# Poactuator_Connectors.net
KiCad netlist of a schematic drawn in Altium Designer
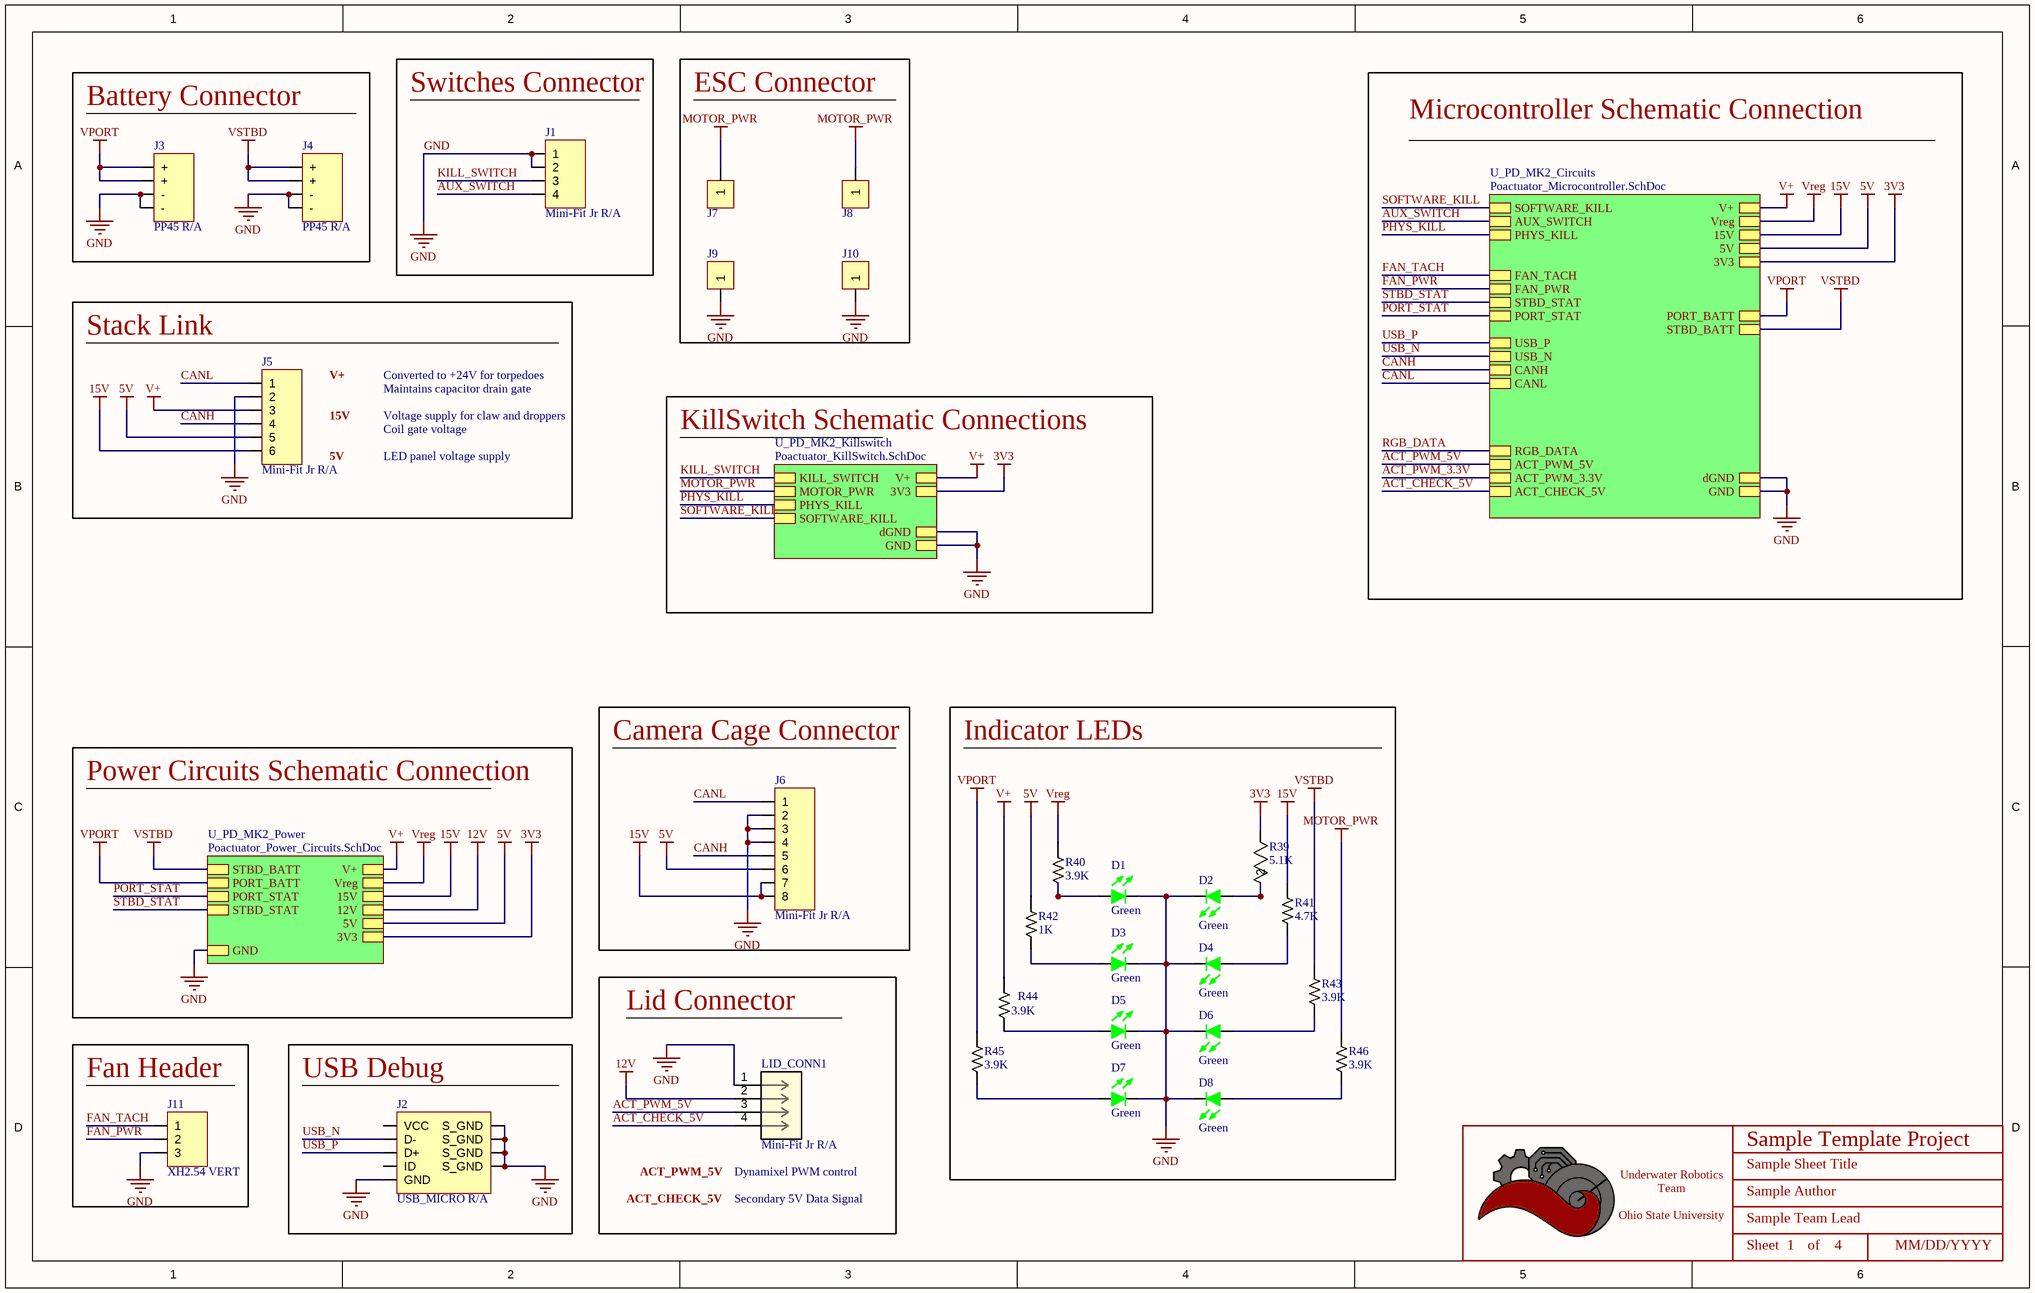
[diagram p0: Poactuator_Connectors.SchDoc]

(export (version "E")
  (design (tool "Eeschema 10.0.6"))
  (components
    (comp (ref "D1")
      (value "IN-S63AT5G")
      (footprint "LED_0603")
      (description "LED Green Vf= 3V If = 0.005A\r\nIN-S63AT5G")
      (fields (field (name "COLOR") "Green") (field (name "MADE BY") "Robert Pafford"))
      (libsource (lib "Diodes") (part "LED_Green_0603_3V"))
    )
    (comp (ref "D2")
      (value "IN-S63AT5G")
      (footprint "LED_0603")
      (description "LED Green Vf= 3V If = 0.005A\r\nIN-S63AT5G")
      (fields (field (name "COLOR") "Green") (field (name "MADE BY") "Robert Pafford"))
      (libsource (lib "Diodes") (part "LED_Green_0603_3V"))
    )
    (comp (ref "D3")
      (value "IN-S63AT5G")
      (footprint "LED_0603")
      (description "LED Green Vf= 3V If = 0.005A\r\nIN-S63AT5G")
      (fields (field (name "COLOR") "Green") (field (name "MADE BY") "Robert Pafford"))
      (libsource (lib "Diodes") (part "LED_Green_0603_3V"))
    )
    (comp (ref "D4")
      (value "IN-S63AT5G")
      (footprint "LED_0603")
      (description "LED Green Vf= 3V If = 0.005A\r\nIN-S63AT5G")
      (fields (field (name "COLOR") "Green") (field (name "MADE BY") "Robert Pafford"))
      (libsource (lib "Diodes") (part "LED_Green_0603_3V"))
    )
    (comp (ref "D5")
      (value "IN-S63AT5G")
      (footprint "LED_0603")
      (description "LED Green Vf= 3V If = 0.005A\r\nIN-S63AT5G")
      (fields (field (name "COLOR") "Green") (field (name "MADE BY") "Robert Pafford"))
      (libsource (lib "Diodes") (part "LED_Green_0603_3V"))
    )
    (comp (ref "D6")
      (value "IN-S63AT5G")
      (footprint "LED_0603")
      (description "LED Green Vf= 3V If = 0.005A\r\nIN-S63AT5G")
      (fields (field (name "COLOR") "Green") (field (name "MADE BY") "Robert Pafford"))
      (libsource (lib "Diodes") (part "LED_Green_0603_3V"))
    )
    (comp (ref "D7")
      (value "IN-S63AT5G")
      (footprint "LED_0603")
      (description "LED Green Vf= 3V If = 0.005A\r\nIN-S63AT5G")
      (fields (field (name "COLOR") "Green") (field (name "MADE BY") "Robert Pafford"))
      (libsource (lib "Diodes") (part "LED_Green_0603_3V"))
    )
    (comp (ref "D8")
      (value "IN-S63AT5G")
      (footprint "LED_0603")
      (description "LED Green Vf= 3V If = 0.005A\r\nIN-S63AT5G")
      (fields (field (name "COLOR") "Green") (field (name "MADE BY") "Robert Pafford"))
      (libsource (lib "Diodes") (part "LED_Green_0603_3V"))
    )
    (comp (ref "J1")
      (value "Mini-Fit Jr R/A")
      (footprint "CONN_MOLEX_MINIFIT JR_4 POS_R/A")
      (description "Molex Minifit Jr. 5569 \r\n4 Pos R/A Natural")
      (fields (field (name "MANUFACTURER") "Molex") (field (name "CREATED BY") "Flip B"))
      (libsource (lib "Connectors") (part "CONN_MOLEX_MINIFIT JR_4POS_R/A"))
    )
    (comp (ref "J2")
      (value "USB_MICRO R/A")
      (footprint "CONN_MINIUSB")
      (description "Amphenol Micro USB-B\r\nUSB2.0 5 Pin Right Angle SMD")
      (fields (field (name "MANUFACTURER") "Amphenol") (field (name "CREATED BY") "Flip B"))
      (libsource (lib "Connectors") (part "CONN_MICROUSB"))
    )
    (comp (ref "J3")
      (value "PP45 R/A")
      (footprint "CONN_ANDERSON_PP45_4 POS_R/A")
      (description "Anderson PP45\r\n4 Pos R/A Red/Black")
      (fields (field (name "MANUFACTURER") "Anderson") (field (name "CREATED BY") "Flip B"))
      (libsource (lib "Connectors") (part "CONN_ANDERSON_2x2_R/A"))
    )
    (comp (ref "J4")
      (value "PP45 R/A")
      (footprint "CONN_ANDERSON_PP45_4 POS_R/A")
      (description "Anderson PP45\r\n4 Pos R/A Red/Black")
      (fields (field (name "MANUFACTURER") "Anderson") (field (name "CREATED BY") "Flip B"))
      (libsource (lib "Connectors") (part "CONN_ANDERSON_2x2_R/A"))
    )
    (comp (ref "J5")
      (value "Mini-Fit Jr R/A")
      (footprint "CONN_MOLEX_MINIFIT JR_6 POS_R/A")
      (description "Molex Minifit Jr. 5569 \r\n6 Pos R/A Natural")
      (fields (field (name "MANUFACTURER") "Molex") (field (name "CREATED BY") "Flip B"))
      (libsource (lib "Connectors") (part "CONN_MOLEX_MINIFIT JR_6POS_R/A"))
    )
    (comp (ref "J6")
      (value "Mini-Fit Jr R/A")
      (footprint "CONN_MOLEX_MINIFIT JR_8 POS_R/A")
      (description "Molex Minifit Jr. 5569 \r\n8 Pos R/A Natural")
      (fields (field (name "MANUFACTURER") "Molex") (field (name "CREATED BY") "Flip B"))
      (libsource (lib "Connectors") (part "CONN_MOLEX_MINIFIT JR_8POS_R/A"))
    )
    (comp (ref "J7")
      (value "Redcube M4 Term 85A")
      (footprint "Redcube M4 Term 85A")
      (fields (field (name "CREATED BY") "Nahtan Ayer"))
      (libsource (lib "") (part "Redcube M4 Term 85A_1"))
    )
    (comp (ref "J8")
      (value "Redcube M4 Term 85A")
      (footprint "Redcube M4 Term 85A")
      (fields (field (name "CREATED BY") "Nahtan Ayer"))
      (libsource (lib "") (part "Redcube M4 Term 85A_1"))
    )
    (comp (ref "J9")
      (value "Redcube M4 Term 85A")
      (footprint "Redcube M4 Term 85A")
      (fields (field (name "CREATED BY") "Nahtan Ayer"))
      (libsource (lib "Connectors") (part "Redcube M4 Term 85A"))
    )
    (comp (ref "J10")
      (value "Redcube M4 Term 85A")
      (footprint "Redcube M4 Term 85A")
      (fields (field (name "CREATED BY") "Nahtan Ayer"))
      (libsource (lib "Connectors") (part "Redcube M4 Term 85A"))
    )
    (comp (ref "J11")
      (value "XH2.54 VERT")
      (footprint "CONN_JST_XH254_3POS_VERT")
      (description "JST XH 2.54mm Pitch 3 Pos Vertical")
      (fields (field (name "MANUFACTURER") "JST") (field (name "CREATED BY") "Robert P"))
      (libsource (lib "Connectors") (part "CONN_JST_XH254_3POS_VERT"))
    )
    (comp (ref "LID_CONN1")
      (value "Mini-Fit Jr R/A")
      (footprint "CONN HEADER R/A 4POS 4.2MM")
      (description "Mini-Fit Jr Connector Header Through Hole, Right Angle 4 position 0.165\" (4.20mm)")
      (fields (field (name "MANUFACTURER") "Molex") (field (name "CREATED BY") "Zach Ramsey"))
      (libsource (lib "Connectors") (part "CONN HEADER R/A 4POS 4.2MM"))
    )
    (comp (ref "R39")
      (value "5.1K")
      (footprint "RC0603N_PAN")
      (description "5.1 kOhms ±0.1% 0.1W, 1/10W Chip Resistor 0603 (1608 Metric) Automotive AEC-Q200 Thin Film")
      (fields
        (field (name "MANUFACTURER_PART_NUMBER") "ERA-3AEB512V")
        (field (name "COPYRIGHT") "Copyright (C) 2023 Ultra Librarian. All rights reserved.")
      )
      (libsource (lib "Resistors") (part "ERA-3AEB512V_2"))
    )
    (comp (ref "R40")
      (value "3.9k Ohm 5% 1/10W")
      (footprint "RESISTOR_0603")
      (description "RES 3.9k OHM 1% 1/10W 0603")
      (fields
        (field (name "TOLERANCE") "+/- 1%")
        (field (name "VALUE  (OHMS)") "3.9K")
        (field (name "MADE BY") "Robert Pafford")
      )
      (libsource (lib "Resistors") (part "RESISTOR_3.9K_0603"))
    )
    (comp (ref "R41")
      (value "4.7k Ohm 5% 1/10W")
      (footprint "RESISTOR_0603")
      (description "RES 4.7k OHM 5% 1/10W 0603")
      (fields
        (field (name "TOLERANCE") "+/- 5%")
        (field (name "VALUE  (OHMS)") "4.7K")
        (field (name "MADE BY") "Robert Pafford")
      )
      (libsource (lib "Resistors") (part "RESISTOR_4.7K_0603"))
    )
    (comp (ref "R42")
      (value "1k Ohm 5% 1/8W")
      (footprint "RESISTOR_0603")
      (description "RES 1k OHM 5% 1/8W 0603")
      (fields
        (field (name "TOLERANCE") "+/- 5%")
        (field (name "VALUE  (OHMS)") "1K")
        (field (name "MADE BY") "Robert Pafford")
      )
      (libsource (lib "Resistors") (part "RESISTOR_1K_0603"))
    )
    (comp (ref "R43")
      (value "3.9k Ohm 5% 1/10W")
      (footprint "RESISTOR_0603")
      (description "RES 3.9k OHM 1% 1/10W 0603")
      (fields
        (field (name "TOLERANCE") "+/- 1%")
        (field (name "VALUE  (OHMS)") "3.9K")
        (field (name "MADE BY") "Robert Pafford")
      )
      (libsource (lib "Resistors") (part "RESISTOR_3.9K_0603"))
    )
    (comp (ref "R44")
      (value "3.9k Ohm 5% 1/10W")
      (footprint "RESISTOR_0603")
      (description "RES 3.9k OHM 1% 1/10W 0603")
      (fields
        (field (name "TOLERANCE") "+/- 1%")
        (field (name "VALUE  (OHMS)") "3.9K")
        (field (name "MADE BY") "Robert Pafford")
      )
      (libsource (lib "Resistors") (part "RESISTOR_3.9K_0603"))
    )
    (comp (ref "R45")
      (value "3.9k Ohm 5% 1/10W")
      (footprint "RESISTOR_0603")
      (description "RES 3.9k OHM 1% 1/10W 0603")
      (fields
        (field (name "TOLERANCE") "+/- 1%")
        (field (name "VALUE  (OHMS)") "3.9K")
        (field (name "MADE BY") "Robert Pafford")
      )
      (libsource (lib "Resistors") (part "RESISTOR_3.9K_0603"))
    )
    (comp (ref "R46")
      (value "3.9k Ohm 5% 1/10W")
      (footprint "RESISTOR_0603")
      (description "RES 3.9k OHM 1% 1/10W 0603")
      (fields
        (field (name "TOLERANCE") "+/- 1%")
        (field (name "VALUE  (OHMS)") "3.9K")
        (field (name "MADE BY") "Robert Pafford")
      )
      (libsource (lib "Resistors") (part "RESISTOR_3.9K_0603"))
    )
  )
  (nets
    (net (code "1") (name "/ACT_CHECK_5V") (class "Default")
      (node (ref "LID_CONN1") (pin "4") (pinfunction "4_4") (pintype "passive"))
    )
    (net (code "3") (name "/ACT_PWM_5V") (class "Default")
      (node (ref "LID_CONN1") (pin "3") (pinfunction "3_3") (pintype "passive"))
    )
    (net (code "4") (name "/AUX_SWITCH") (class "Default")
      (node (ref "J1") (pin "4") (pinfunction "4_4") (pintype "passive"))
    )
    (net (code "5") (name "/CANH") (class "Default")
      (node (ref "J5") (pin "4") (pinfunction "4_4") (pintype "passive"))
      (node (ref "J6") (pin "5") (pinfunction "5_5") (pintype "passive"))
    )
    (net (code "6") (name "/CANL") (class "Default")
      (node (ref "J5") (pin "1") (pinfunction "1_1") (pintype "passive"))
      (node (ref "J6") (pin "1") (pinfunction "1_1") (pintype "passive"))
    )
    (net (code "7") (name "/FAN_PWR") (class "Default")
      (node (ref "J11") (pin "2") (pinfunction "2_2") (pintype "passive"))
    )
    (net (code "8") (name "/FAN_TACH") (class "Default")
      (node (ref "J11") (pin "1") (pinfunction "1_1") (pintype "passive"))
    )
    (net (code "9") (name "/KILL_SWITCH") (class "Default")
      (node (ref "J1") (pin "3") (pinfunction "3_3") (pintype "passive"))
    )
    (net (code "15") (name "/USB_N") (class "Default")
      (node (ref "J2") (pin "2") (pinfunction "D-_2") (pintype "passive"))
    )
    (net (code "16") (name "/USB_P") (class "Default")
      (node (ref "J2") (pin "3") (pinfunction "D+_3") (pintype "passive"))
    )
    (net (code "17") (name "3V3") (class "Default")
      (node (ref "R39") (pin "1") (pinfunction "1_1") (pintype "passive"))
    )
    (net (code "18") (name "5V") (class "Default")
      (node (ref "J5") (pin "5") (pinfunction "5_5") (pintype "passive"))
      (node (ref "J6") (pin "6") (pinfunction "6_6") (pintype "passive"))
      (node (ref "R42") (pin "1") (pinfunction "1_1") (pintype "passive"))
    )
    (net (code "19") (name "12V") (class "Default")
      (node (ref "LID_CONN1") (pin "2") (pinfunction "2_2") (pintype "passive"))
    )
    (net (code "20") (name "15V") (class "Default")
      (node (ref "J5") (pin "6") (pinfunction "6_6") (pintype "passive"))
      (node (ref "J6") (pin "7") (pinfunction "7_7") (pintype "passive"))
      (node (ref "J6") (pin "8") (pinfunction "8_8") (pintype "passive"))
      (node (ref "R41") (pin "1") (pinfunction "1_1") (pintype "passive"))
    )
    (net (code "21") (name "GND") (class "Default")
      (node (ref "D1") (pin "2") (pinfunction "2_2") (pintype "passive"))
      (node (ref "D2") (pin "2") (pinfunction "2_2") (pintype "passive"))
      (node (ref "D3") (pin "2") (pinfunction "2_2") (pintype "passive"))
      (node (ref "D4") (pin "2") (pinfunction "2_2") (pintype "passive"))
      (node (ref "D5") (pin "2") (pinfunction "2_2") (pintype "passive"))
      (node (ref "D6") (pin "2") (pinfunction "2_2") (pintype "passive"))
      (node (ref "D7") (pin "2") (pinfunction "2_2") (pintype "passive"))
      (node (ref "D8") (pin "2") (pinfunction "2_2") (pintype "passive"))
      (node (ref "J1") (pin "1") (pinfunction "1_1") (pintype "passive"))
      (node (ref "J1") (pin "2") (pinfunction "2_2") (pintype "passive"))
      (node (ref "J10") (pin "1") (pinfunction "1_1") (pintype "passive"))
      (node (ref "J11") (pin "3") (pinfunction "3_3") (pintype "passive"))
      (node (ref "J2") (pin "5") (pinfunction "GND_5") (pintype "passive"))
      (node (ref "J2") (pin "6") (pinfunction "S_GND_6") (pintype "passive"))
      (node (ref "J2") (pin "7") (pinfunction "S_GND_7") (pintype "passive"))
      (node (ref "J2") (pin "8") (pinfunction "S_GND_8") (pintype "passive"))
      (node (ref "J2") (pin "9") (pinfunction "S_GND_9") (pintype "passive"))
      (node (ref "J3") (pin "3") (pinfunction "-_3") (pintype "passive"))
      (node (ref "J3") (pin "4") (pinfunction "-_4") (pintype "passive"))
      (node (ref "J4") (pin "3") (pinfunction "-_3") (pintype "passive"))
      (node (ref "J4") (pin "4") (pinfunction "-_4") (pintype "passive"))
      (node (ref "J5") (pin "2") (pinfunction "2_2") (pintype "passive"))
      (node (ref "J6") (pin "2") (pinfunction "2_2") (pintype "passive"))
      (node (ref "J6") (pin "3") (pinfunction "3_3") (pintype "passive"))
      (node (ref "J6") (pin "4") (pinfunction "4_4") (pintype "passive"))
      (node (ref "J9") (pin "1") (pinfunction "1_1") (pintype "passive"))
      (node (ref "LID_CONN1") (pin "1") (pinfunction "1_1") (pintype "passive"))
    )
    (net (code "22") (name "MOTOR_PWR") (class "Default")
      (node (ref "J7") (pin "1") (pinfunction "1_1") (pintype "passive"))
      (node (ref "J8") (pin "1") (pinfunction "1_1") (pintype "passive"))
      (node (ref "R46") (pin "1") (pinfunction "1_1") (pintype "passive"))
    )
    (net (code "23") (name "Net-(D1-Pad1)") (class "Default")
      (node (ref "D1") (pin "1") (pinfunction "1_1") (pintype "passive"))
      (node (ref "R40") (pin "2") (pinfunction "2_2") (pintype "passive"))
    )
    (net (code "24") (name "Net-(D2-Pad1)") (class "Default")
      (node (ref "D2") (pin "1") (pinfunction "1_1") (pintype "passive"))
      (node (ref "R39") (pin "2") (pinfunction "2_2") (pintype "passive"))
    )
    (net (code "25") (name "Net-(D3-Pad1)") (class "Default")
      (node (ref "D3") (pin "1") (pinfunction "1_1") (pintype "passive"))
      (node (ref "R42") (pin "2") (pinfunction "2_2") (pintype "passive"))
    )
    (net (code "26") (name "Net-(D4-Pad1)") (class "Default")
      (node (ref "D4") (pin "1") (pinfunction "1_1") (pintype "passive"))
      (node (ref "R41") (pin "2") (pinfunction "2_2") (pintype "passive"))
    )
    (net (code "27") (name "Net-(D5-Pad1)") (class "Default")
      (node (ref "D5") (pin "1") (pinfunction "1_1") (pintype "passive"))
      (node (ref "R44") (pin "2") (pinfunction "2_2") (pintype "passive"))
    )
    (net (code "28") (name "Net-(D6-Pad1)") (class "Default")
      (node (ref "D6") (pin "1") (pinfunction "1_1") (pintype "passive"))
      (node (ref "R43") (pin "2") (pinfunction "2_2") (pintype "passive"))
    )
    (net (code "29") (name "Net-(D7-Pad1)") (class "Default")
      (node (ref "D7") (pin "1") (pinfunction "1_1") (pintype "passive"))
      (node (ref "R45") (pin "2") (pinfunction "2_2") (pintype "passive"))
    )
    (net (code "30") (name "Net-(D8-Pad1)") (class "Default")
      (node (ref "D8") (pin "1") (pinfunction "1_1") (pintype "passive"))
      (node (ref "R46") (pin "2") (pinfunction "2_2") (pintype "passive"))
    )
    (net (code "31") (name "V+") (class "Default")
      (node (ref "J5") (pin "3") (pinfunction "3_3") (pintype "passive"))
      (node (ref "R44") (pin "1") (pinfunction "1_1") (pintype "passive"))
    )
    (net (code "32") (name "VPORT") (class "Default")
      (node (ref "J3") (pin "1") (pinfunction "+_1") (pintype "passive"))
      (node (ref "J3") (pin "2") (pinfunction "+_2") (pintype "passive"))
      (node (ref "R45") (pin "1") (pinfunction "1_1") (pintype "passive"))
    )
    (net (code "33") (name "VSTBD") (class "Default")
      (node (ref "J4") (pin "1") (pinfunction "+_1") (pintype "passive"))
      (node (ref "J4") (pin "2") (pinfunction "+_2") (pintype "passive"))
      (node (ref "R43") (pin "1") (pinfunction "1_1") (pintype "passive"))
    )
    (net (code "34") (name "Vreg") (class "Default")
      (node (ref "R40") (pin "1") (pinfunction "1_1") (pintype "passive"))
    )
    (net (code "35") (name "unconnected-(J2-ID-Pad4)") (class "Default")
      (node (ref "J2") (pin "4") (pinfunction "ID_4") (pintype "passive"))
    )
    (net (code "36") (name "unconnected-(J2-VCC-Pad1)") (class "Default")
      (node (ref "J2") (pin "1") (pinfunction "VCC_1") (pintype "passive"))
    )
  )
)
